# CAN-to-CAN.net
KiCad netlist of a schematic drawn in Altium Designer
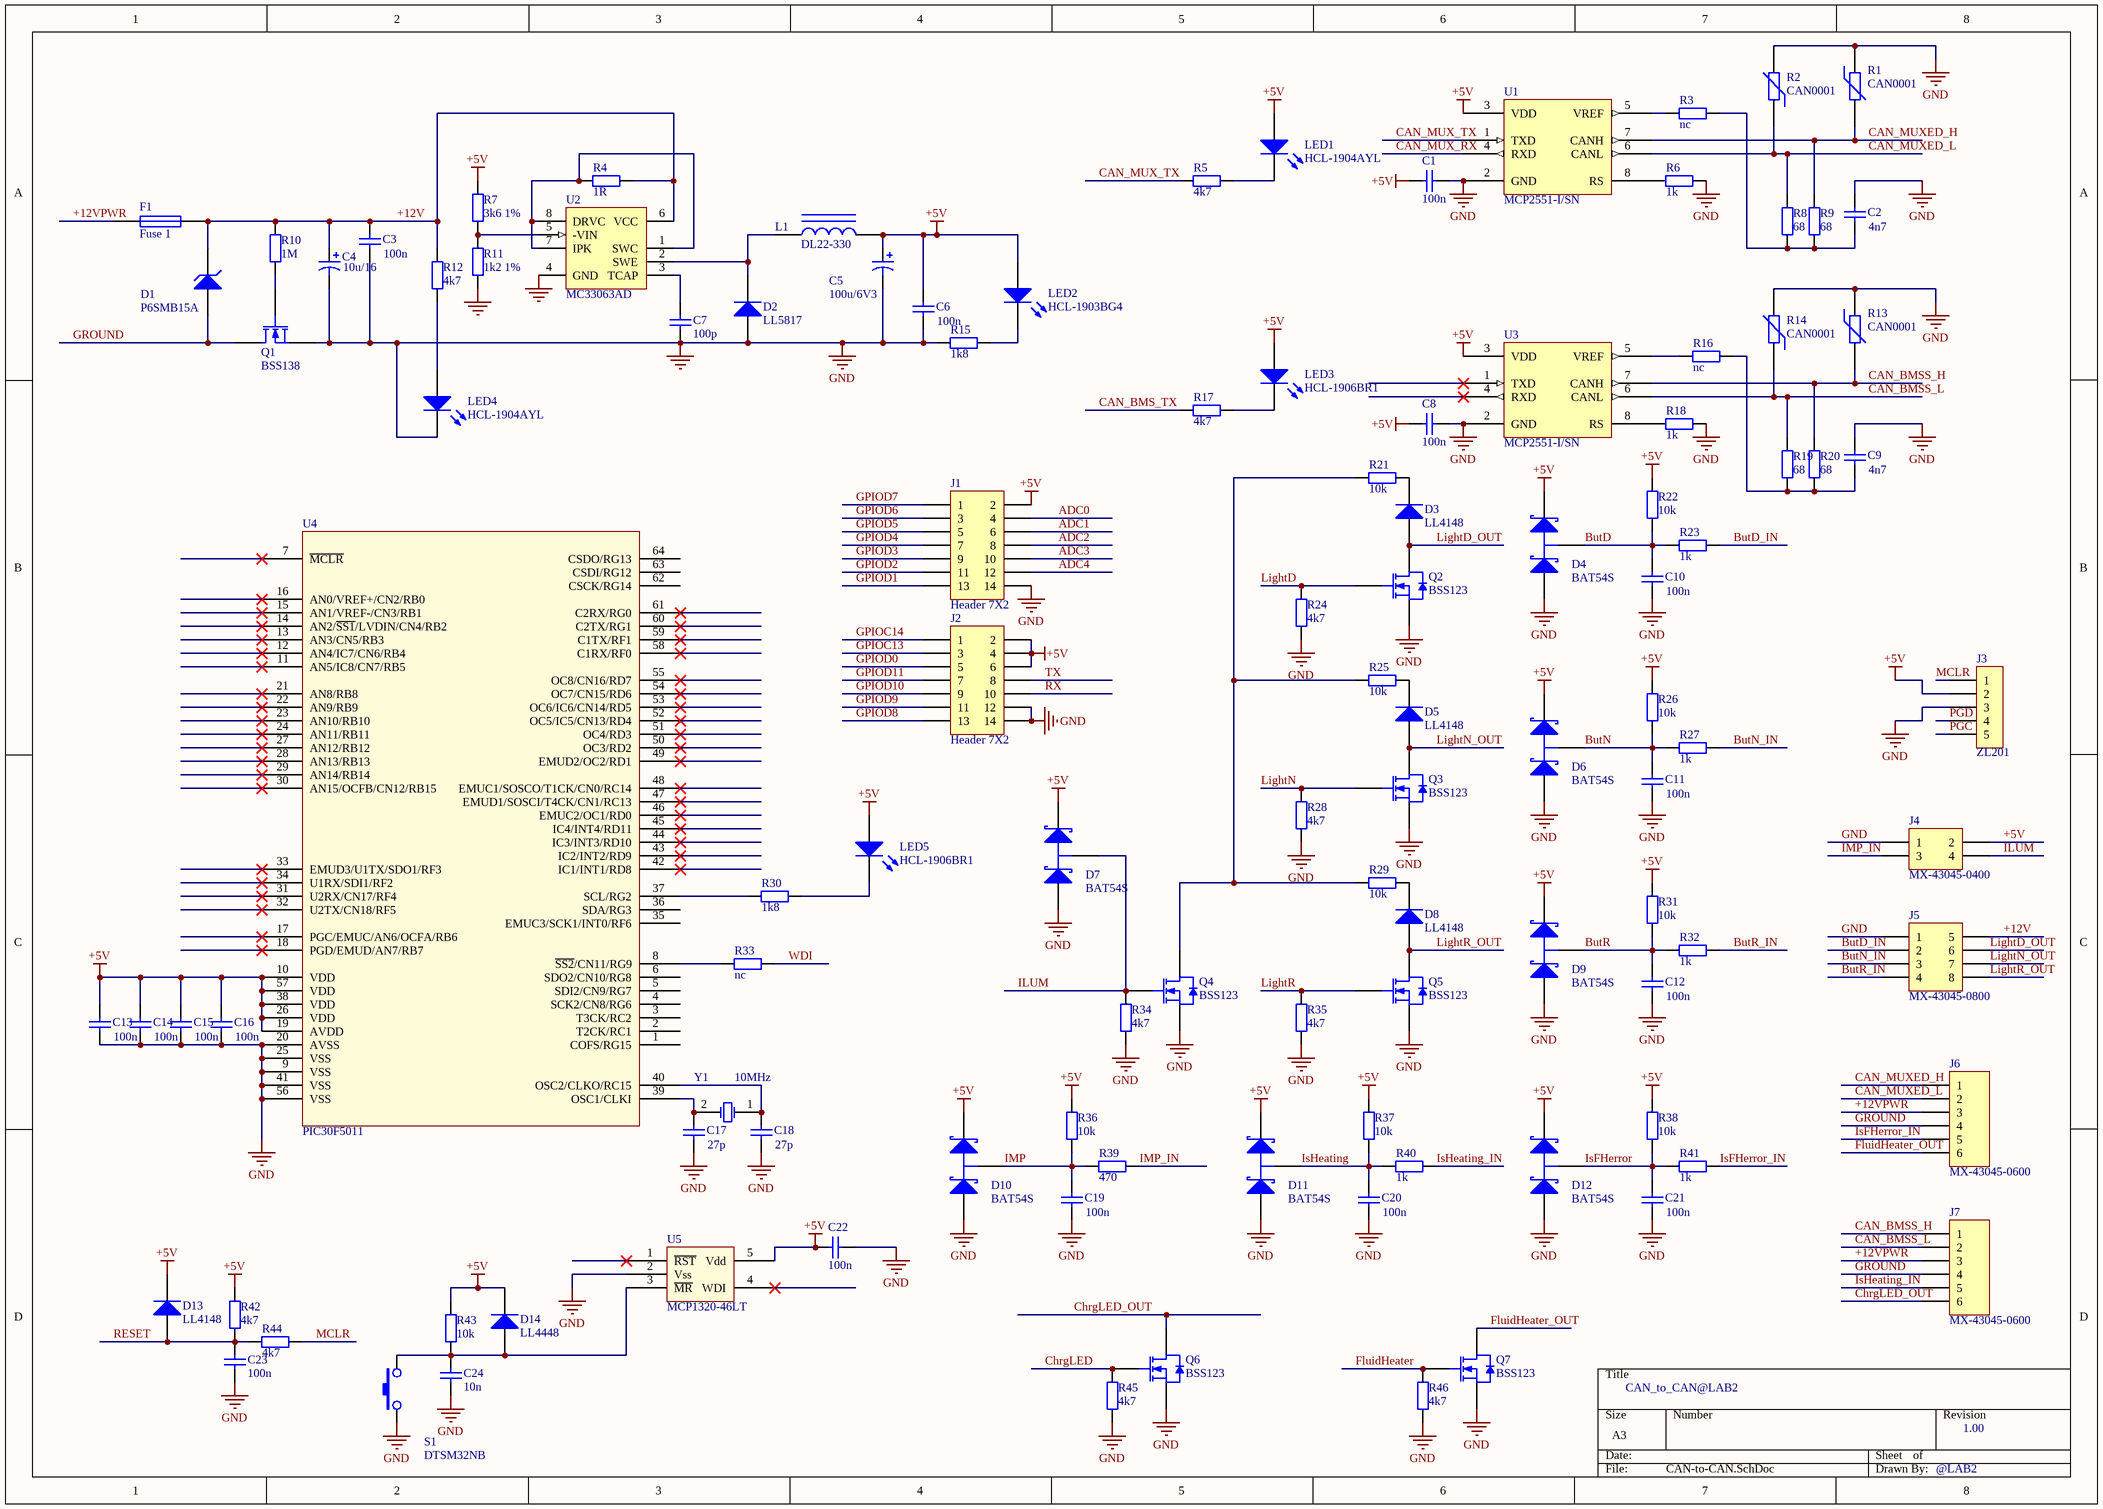
[diagram p0: CAN-to-CAN.SchDoc]

(export (version "E")
  (design (tool "Eeschema 10.0.6"))
  (components
    (comp (ref "C1")
      (value "100n")
      (footprint "0603")
      (description "Capacitor")
      (fields (field (name "PUBLISHER") "Altium Limited"))
      (libsource (lib "Miscellaneous Devices") (part "Cap"))
    )
    (comp (ref "C2")
      (value "4n7")
      (footprint "0603")
      (description "Capacitor")
      (fields (field (name "PUBLISHER") "Altium Limited"))
      (libsource (lib "Miscellaneous Devices") (part "Cap"))
    )
    (comp (ref "C3")
      (value "100n")
      (footprint "0402")
      (description "Capacitor")
      (fields (field (name "PUBLISHER") "Altium Limited"))
      (libsource (lib "Miscellaneous Devices") (part "Cap"))
    )
    (comp (ref "C4")
      (value "10u/16")
      (footprint "0402")
      (description "Polarized Capacitor (Radial)")
      (fields (field (name "PUBLISHER") "Altium Limited"))
      (libsource (lib "Miscellaneous Devices") (part "Cap Pol1"))
    )
    (comp (ref "C5")
      (value "100u/6V3")
      (footprint "0402")
      (description "Polarized Capacitor (Radial)")
      (fields (field (name "PUBLISHER") "Altium Limited"))
      (libsource (lib "Miscellaneous Devices") (part "Cap Pol1"))
    )
    (comp (ref "C6")
      (value "100n")
      (footprint "0603")
      (description "Capacitor")
      (fields (field (name "PUBLISHER") "Altium Limited"))
      (libsource (lib "Miscellaneous Devices") (part "Cap"))
    )
    (comp (ref "C7")
      (value "100p")
      (footprint "0603")
      (description "Capacitor")
      (fields (field (name "PUBLISHER") "Altium Limited"))
      (libsource (lib "Miscellaneous Devices") (part "Cap"))
    )
    (comp (ref "C8")
      (value "100n")
      (footprint "0603")
      (description "Capacitor")
      (fields (field (name "PUBLISHER") "Altium Limited"))
      (libsource (lib "Miscellaneous Devices") (part "Cap"))
    )
    (comp (ref "C9")
      (value "4n7")
      (footprint "0603")
      (description "Capacitor")
      (fields (field (name "PUBLISHER") "Altium Limited"))
      (libsource (lib "Miscellaneous Devices") (part "Cap"))
    )
    (comp (ref "C10")
      (value "100n")
      (footprint "0603")
      (description "Capacitor")
      (fields (field (name "PUBLISHER") "Altium Limited"))
      (libsource (lib "Miscellaneous Devices") (part "Cap"))
    )
    (comp (ref "C11")
      (value "100n")
      (footprint "0603")
      (description "Capacitor")
      (fields (field (name "PUBLISHER") "Altium Limited"))
      (libsource (lib "Miscellaneous Devices") (part "Cap"))
    )
    (comp (ref "C12")
      (value "100n")
      (footprint "0603")
      (description "Capacitor")
      (fields (field (name "PUBLISHER") "Altium Limited"))
      (libsource (lib "Miscellaneous Devices") (part "Cap"))
    )
    (comp (ref "C13")
      (value "100n")
      (footprint "0603")
      (description "Capacitor")
      (fields (field (name "PUBLISHER") "Altium Limited"))
      (libsource (lib "Miscellaneous Devices") (part "Cap"))
    )
    (comp (ref "C14")
      (value "100n")
      (footprint "0603")
      (description "Capacitor")
      (fields (field (name "PUBLISHER") "Altium Limited"))
      (libsource (lib "Miscellaneous Devices") (part "Cap"))
    )
    (comp (ref "C15")
      (value "100n")
      (footprint "0603")
      (description "Capacitor")
      (fields (field (name "PUBLISHER") "Altium Limited"))
      (libsource (lib "Miscellaneous Devices") (part "Cap"))
    )
    (comp (ref "C16")
      (value "100n")
      (footprint "0603")
      (description "Capacitor")
      (fields (field (name "PUBLISHER") "Altium Limited"))
      (libsource (lib "Miscellaneous Devices") (part "Cap"))
    )
    (comp (ref "C17")
      (value "27p")
      (footprint "0603")
      (description "Capacitor")
      (fields (field (name "PUBLISHER") "Altium Limited"))
      (libsource (lib "Miscellaneous Devices") (part "Cap"))
    )
    (comp (ref "C18")
      (value "27p")
      (footprint "0603")
      (description "Capacitor")
      (fields (field (name "PUBLISHER") "Altium Limited"))
      (libsource (lib "Miscellaneous Devices") (part "Cap"))
    )
    (comp (ref "C19")
      (value "100n")
      (footprint "0603")
      (description "Capacitor")
      (fields (field (name "PUBLISHER") "Altium Limited"))
      (libsource (lib "Miscellaneous Devices") (part "Cap"))
    )
    (comp (ref "C20")
      (value "100n")
      (footprint "0603")
      (description "Capacitor")
      (fields (field (name "PUBLISHER") "Altium Limited"))
      (libsource (lib "Miscellaneous Devices") (part "Cap"))
    )
    (comp (ref "C21")
      (value "100n")
      (footprint "0603")
      (description "Capacitor")
      (fields (field (name "PUBLISHER") "Altium Limited"))
      (libsource (lib "Miscellaneous Devices") (part "Cap"))
    )
    (comp (ref "C22")
      (value "100n")
      (footprint "0603")
      (description "Capacitor")
      (fields (field (name "PUBLISHER") "Altium Limited"))
      (libsource (lib "Miscellaneous Devices") (part "Cap"))
    )
    (comp (ref "C23")
      (value "100n")
      (footprint "0603")
      (description "Capacitor")
      (fields (field (name "PUBLISHER") "Altium Limited"))
      (libsource (lib "Miscellaneous Devices") (part "Cap"))
    )
    (comp (ref "C24")
      (value "10n")
      (footprint "0603")
      (description "Capacitor")
      (fields (field (name "PUBLISHER") "Altium Limited"))
      (libsource (lib "Miscellaneous Devices") (part "Cap"))
    )
    (comp (ref "D1")
      (value "P6SMB15A")
      (footprint "SMB")
      (description "Zener Diode")
      (fields (field (name "PUBLISHER") "Altium Limited"))
      (libsource (lib "Miscellaneous Devices") (part "D Zener"))
    )
    (comp (ref "D2")
      (value "LL5817")
      (footprint "DIODE_SMC")
      (description "High Conductance Fast Diode")
      (fields (field (name "PUBLISHER") "Altium Limited"))
      (libsource (lib "FSC Discrete Diode") (part "1N4148"))
    )
    (comp (ref "D3")
      (value "LL4148")
      (footprint "DIODE_SMC")
      (description "High Conductance Fast Diode")
      (fields (field (name "PUBLISHER") "Altium Limited"))
      (libsource (lib "FSC Discrete Diode") (part "1N4148"))
    )
    (comp (ref "D4")
      (value "BAT54S")
      (footprint "SOT-23_M")
      (description "Schottky Barrier Double Diode")
      (fields (field (name "PUBLISHER") "Altium Limited"))
      (libsource (lib "Philips Discrete Diode - Schottky") (part "BAT54S"))
    )
    (comp (ref "D5")
      (value "LL4148")
      (footprint "DIODE_SMC")
      (description "High Conductance Fast Diode")
      (fields (field (name "PUBLISHER") "Altium Limited"))
      (libsource (lib "FSC Discrete Diode") (part "1N4148"))
    )
    (comp (ref "D6")
      (value "BAT54S")
      (footprint "SOT23_M")
      (description "Schottky Barrier Double Diode")
      (fields (field (name "PUBLISHER") "Altium Limited"))
      (libsource (lib "Philips Discrete Diode - Schottky") (part "BAT54S"))
    )
    (comp (ref "D7")
      (value "BAT54S")
      (footprint "SOT23_M")
      (description "Schottky Barrier Double Diode")
      (fields (field (name "PUBLISHER") "Altium Limited"))
      (libsource (lib "Philips Discrete Diode - Schottky") (part "BAT54S"))
    )
    (comp (ref "D8")
      (value "LL4148")
      (footprint "DIODE_SMC")
      (description "High Conductance Fast Diode")
      (fields (field (name "PUBLISHER") "Altium Limited"))
      (libsource (lib "FSC Discrete Diode") (part "1N4148"))
    )
    (comp (ref "D9")
      (value "BAT54S")
      (footprint "SOT23_M")
      (description "Schottky Barrier Double Diode")
      (fields (field (name "PUBLISHER") "Altium Limited"))
      (libsource (lib "Philips Discrete Diode - Schottky") (part "BAT54S"))
    )
    (comp (ref "D10")
      (value "BAT54S")
      (footprint "SOT23_M")
      (description "Schottky Barrier Double Diode")
      (fields (field (name "PUBLISHER") "Altium Limited"))
      (libsource (lib "Philips Discrete Diode - Schottky") (part "BAT54S"))
    )
    (comp (ref "D11")
      (value "BAT54S")
      (footprint "SOT23_M")
      (description "Schottky Barrier Double Diode")
      (fields (field (name "PUBLISHER") "Altium Limited"))
      (libsource (lib "Philips Discrete Diode - Schottky") (part "BAT54S"))
    )
    (comp (ref "D12")
      (value "BAT54S")
      (footprint "SOT23_M")
      (description "Schottky Barrier Double Diode")
      (fields (field (name "PUBLISHER") "Altium Limited"))
      (libsource (lib "Philips Discrete Diode - Schottky") (part "BAT54S"))
    )
    (comp (ref "D13")
      (value "LL4148")
      (footprint "DIODE_SMC")
      (description "High Conductance Fast Diode")
      (fields (field (name "PUBLISHER") "Altium Limited"))
      (libsource (lib "FSC Discrete Diode") (part "1N4148"))
    )
    (comp (ref "D14")
      (value "LL4448")
      (footprint "DIODE_SMC")
      (description "Default Diode")
      (fields (field (name "PUBLISHER") "Altium Limited"))
      (libsource (lib "Miscellaneous Devices") (part "Diode"))
    )
    (comp (ref "F1")
      (value "Fuse 1")
      (footprint "1812")
      (description "Fuse")
      (fields (field (name "PUBLISHER") "Altium Limited"))
      (libsource (lib "Miscellaneous Devices") (part "Fuse 1"))
    )
    (comp (ref "J1")
      (value "Header 7X2")
      (footprint "HDR2X7")
      (description "Header, 7-Pin, Dual row")
      (fields (field (name "PUBLISHER") "Altium Limited"))
      (libsource (lib "Miscellaneous Connectors") (part "Header 7X2"))
    )
    (comp (ref "J2")
      (value "Header 7X2")
      (footprint "HDR2X7")
      (description "Header, 7-Pin, Dual row")
      (fields (field (name "PUBLISHER") "Altium Limited"))
      (libsource (lib "Miscellaneous Connectors") (part "Header 7X2"))
    )
    (comp (ref "J3")
      (value "ZL201")
      (footprint "HDR1X5")
      (description "Connector")
      (libsource (lib "*") (part "CON5"))
    )
    (comp (ref "J4")
      (value "MX-43045-0400")
      (footprint "SOT-343_M")
      (description "Header, 2-Pin, Dual row")
      (fields (field (name "PUBLISHER") "Altium Limited"))
      (libsource (lib "Miscellaneous Connectors") (part "Header 2X2"))
    )
    (comp (ref "J5")
      (value "MX-43045-0800")
      (footprint "DB008_M")
      (description "Header, 4-Pin, Dual row")
      (fields (field (name "PUBLISHER") "Altium Limited"))
      (libsource (lib "Miscellaneous Connectors") (part "Header 4X2A"))
    )
    (comp (ref "J6")
      (value "MX-43045-0600")
      (footprint "Miscellaneous Connectors:HDR1X6")
      (description "Header, 6-Pin")
      (fields (field (name "PUBLISHER") "Altium Limited"))
      (libsource (lib "Miscellaneous Connectors") (part "Header 6"))
    )
    (comp (ref "J7")
      (value "MX-43045-0600")
      (footprint "Miscellaneous Connectors:HDR1X6")
      (description "Header, 6-Pin")
      (fields (field (name "PUBLISHER") "Altium Limited"))
      (libsource (lib "Miscellaneous Connectors") (part "Header 6"))
    )
    (comp (ref "L1")
      (value "DL22-330")
      (footprint "INDC1608L")
      (description "Magnetic-Core Inductor")
      (fields (field (name "PUBLISHER") "Altium Limited"))
      (libsource (lib "Miscellaneous Devices") (part "Inductor Iron"))
    )
    (comp (ref "LED1")
      (value "HCL-1904AYL")
      (footprint "0603")
      (description "Typical BLUE SiC LED")
      (fields (field (name "PUBLISHER") "Altium Limited"))
      (libsource (lib "Miscellaneous Devices") (part "LED3"))
    )
    (comp (ref "LED2")
      (value "HCL-1903BG4")
      (footprint "0603")
      (description "Typical BLUE SiC LED")
      (fields (field (name "PUBLISHER") "Altium Limited"))
      (libsource (lib "Miscellaneous Devices") (part "LED3"))
    )
    (comp (ref "LED3")
      (value "HCL-1906BR1")
      (footprint "0603")
      (description "Typical BLUE SiC LED")
      (fields (field (name "PUBLISHER") "Altium Limited"))
      (libsource (lib "Miscellaneous Devices") (part "LED3"))
    )
    (comp (ref "LED4")
      (value "HCL-1904AYL")
      (footprint "0603")
      (description "Typical BLUE SiC LED")
      (fields (field (name "PUBLISHER") "Altium Limited"))
      (libsource (lib "Miscellaneous Devices") (part "LED3"))
    )
    (comp (ref "LED5")
      (value "HCL-1906BR1")
      (footprint "0603")
      (description "Typical BLUE SiC LED")
      (fields (field (name "PUBLISHER") "Altium Limited"))
      (libsource (lib "Miscellaneous Devices") (part "LED3"))
    )
    (comp (ref "Q1")
      (value "BSS138")
      (footprint "SOT23_M")
      (description "N-Channel Enhancement Mode Vertical DMOS FET")
      (fields (field (name "PUBLISHER") "Altium Limited"))
      (libsource (lib "Zetex Discrete MOSFET") (part "BSS138"))
    )
    (comp (ref "Q2")
      (value "BSS123")
      (footprint "SOT23_M")
      (description "N-channel Enhancement Mode Vertical D-MOSFET")
      (fields (field (name "PUBLISHER") "Altium Limited"))
      (libsource (lib "Philips Discrete MOSFET - Low Power") (part "BSS123"))
    )
    (comp (ref "Q3")
      (value "BSS123")
      (footprint "SOT23_M")
      (description "N-channel Enhancement Mode Vertical D-MOSFET")
      (fields (field (name "PUBLISHER") "Altium Limited"))
      (libsource (lib "Philips Discrete MOSFET - Low Power") (part "BSS123"))
    )
    (comp (ref "Q4")
      (value "BSS123")
      (footprint "SOT23_M")
      (description "N-channel Enhancement Mode Vertical D-MOSFET")
      (fields (field (name "PUBLISHER") "Altium Limited"))
      (libsource (lib "Philips Discrete MOSFET - Low Power") (part "BSS123"))
    )
    (comp (ref "Q5")
      (value "BSS123")
      (footprint "SOT23_M")
      (description "N-channel Enhancement Mode Vertical D-MOSFET")
      (fields (field (name "PUBLISHER") "Altium Limited"))
      (libsource (lib "Philips Discrete MOSFET - Low Power") (part "BSS123"))
    )
    (comp (ref "Q6")
      (value "BSS123")
      (footprint "SOT23_M")
      (description "N-channel Enhancement Mode Vertical D-MOSFET")
      (fields (field (name "PUBLISHER") "Altium Limited"))
      (libsource (lib "Philips Discrete MOSFET - Low Power") (part "BSS123"))
    )
    (comp (ref "Q7")
      (value "BSS123")
      (footprint "SOT23_M")
      (description "N-channel Enhancement Mode Vertical D-MOSFET")
      (fields (field (name "PUBLISHER") "Altium Limited"))
      (libsource (lib "Philips Discrete MOSFET - Low Power") (part "BSS123"))
    )
    (comp (ref "R1")
      (value "CAN0001")
      (footprint "0603")
      (description "Varistor (Voltage-Sensitive Resistor)")
      (fields (field (name "PUBLISHER") "Altium Limited"))
      (libsource (lib "Miscellaneous Devices") (part "Res Varistor"))
    )
    (comp (ref "R2")
      (value "CAN0001")
      (footprint "0603")
      (description "Varistor (Voltage-Sensitive Resistor)")
      (fields (field (name "PUBLISHER") "Altium Limited"))
      (libsource (lib "Miscellaneous Devices") (part "Res Varistor"))
    )
    (comp (ref "R3")
      (value "nc")
      (footprint "0603")
      (description "Resistor")
      (fields (field (name "PUBLISHER") "Altium Limited"))
      (libsource (lib "") (part "Res2_3"))
    )
    (comp (ref "R4")
      (value "1R")
      (footprint "12Z-2010")
      (description "Resistor")
      (fields (field (name "PUBLISHER") "Altium Limited"))
      (libsource (lib "") (part "Res2_3"))
    )
    (comp (ref "R5")
      (value "4k7")
      (footprint "0603")
      (description "Resistor")
      (fields (field (name "PUBLISHER") "Altium Limited"))
      (libsource (lib "") (part "Res2_1"))
    )
    (comp (ref "R6")
      (value "1k")
      (footprint "0603")
      (description "Resistor")
      (fields (field (name "PUBLISHER") "Altium Limited"))
      (libsource (lib "") (part "Res2_3"))
    )
    (comp (ref "R7")
      (value "3k6 1%")
      (footprint "0603")
      (description "Resistor")
      (fields (field (name "PUBLISHER") "Altium Limited"))
      (libsource (lib "Miscellaneous Devices") (part "Res2"))
    )
    (comp (ref "R8")
      (value "68")
      (footprint "0603")
      (description "Resistor")
      (fields (field (name "PUBLISHER") "Altium Limited"))
      (libsource (lib "Miscellaneous Devices") (part "Res2"))
    )
    (comp (ref "R9")
      (value "68")
      (footprint "0603")
      (description "Resistor")
      (fields (field (name "PUBLISHER") "Altium Limited"))
      (libsource (lib "Miscellaneous Devices") (part "Res2"))
    )
    (comp (ref "R10")
      (value "1M")
      (footprint "0603")
      (description "Resistor")
      (fields (field (name "PUBLISHER") "Altium Limited"))
      (libsource (lib "Miscellaneous Devices") (part "Res2"))
    )
    (comp (ref "R11")
      (value "1k2 1%")
      (footprint "0603")
      (description "Resistor")
      (fields (field (name "PUBLISHER") "Altium Limited"))
      (libsource (lib "") (part "Res2_2"))
    )
    (comp (ref "R12")
      (value "4k7")
      (footprint "0603")
      (description "Resistor")
      (fields (field (name "PUBLISHER") "Altium Limited"))
      (libsource (lib "Miscellaneous Devices") (part "Res2"))
    )
    (comp (ref "R13")
      (value "CAN0001")
      (footprint "0603")
      (description "Varistor (Voltage-Sensitive Resistor)")
      (fields (field (name "PUBLISHER") "Altium Limited"))
      (libsource (lib "Miscellaneous Devices") (part "Res Varistor"))
    )
    (comp (ref "R14")
      (value "CAN0001")
      (footprint "0603")
      (description "Varistor (Voltage-Sensitive Resistor)")
      (fields (field (name "PUBLISHER") "Altium Limited"))
      (libsource (lib "Miscellaneous Devices") (part "Res Varistor"))
    )
    (comp (ref "R15")
      (value "1k8")
      (footprint "0603")
      (description "Resistor")
      (fields (field (name "PUBLISHER") "Altium Limited"))
      (libsource (lib "") (part "Res2_1"))
    )
    (comp (ref "R16")
      (value "nc")
      (footprint "0603")
      (description "Resistor")
      (fields (field (name "PUBLISHER") "Altium Limited"))
      (libsource (lib "") (part "Res2_3"))
    )
    (comp (ref "R17")
      (value "4k7")
      (footprint "0603")
      (description "Resistor")
      (fields (field (name "PUBLISHER") "Altium Limited"))
      (libsource (lib "") (part "Res2_1"))
    )
    (comp (ref "R18")
      (value "1k")
      (footprint "0603")
      (description "Resistor")
      (fields (field (name "PUBLISHER") "Altium Limited"))
      (libsource (lib "") (part "Res2_3"))
    )
    (comp (ref "R19")
      (value "68")
      (footprint "0603")
      (description "Resistor")
      (fields (field (name "PUBLISHER") "Altium Limited"))
      (libsource (lib "Miscellaneous Devices") (part "Res2"))
    )
    (comp (ref "R20")
      (value "68")
      (footprint "0603")
      (description "Resistor")
      (fields (field (name "PUBLISHER") "Altium Limited"))
      (libsource (lib "Miscellaneous Devices") (part "Res2"))
    )
    (comp (ref "R21")
      (value "10k")
      (footprint "0603")
      (description "Resistor")
      (fields (field (name "PUBLISHER") "Altium Limited"))
      (libsource (lib "") (part "Res2_3"))
    )
    (comp (ref "R22")
      (value "10k")
      (footprint "0603")
      (description "Resistor")
      (fields (field (name "PUBLISHER") "Altium Limited"))
      (libsource (lib "Miscellaneous Devices") (part "Res2"))
    )
    (comp (ref "R23")
      (value "1k")
      (footprint "0603")
      (description "Resistor")
      (fields (field (name "PUBLISHER") "Altium Limited"))
      (libsource (lib "") (part "Res2_1"))
    )
    (comp (ref "R24")
      (value "4k7")
      (footprint "0603")
      (description "Resistor")
      (fields (field (name "PUBLISHER") "Altium Limited"))
      (libsource (lib "Miscellaneous Devices") (part "Res2"))
    )
    (comp (ref "R25")
      (value "10k")
      (footprint "0603")
      (description "Resistor")
      (fields (field (name "PUBLISHER") "Altium Limited"))
      (libsource (lib "") (part "Res2_3"))
    )
    (comp (ref "R26")
      (value "10k")
      (footprint "0603")
      (description "Resistor")
      (fields (field (name "PUBLISHER") "Altium Limited"))
      (libsource (lib "Miscellaneous Devices") (part "Res2"))
    )
    (comp (ref "R27")
      (value "1k")
      (footprint "0603")
      (description "Resistor")
      (fields (field (name "PUBLISHER") "Altium Limited"))
      (libsource (lib "") (part "Res2_1"))
    )
    (comp (ref "R28")
      (value "4k7")
      (footprint "0603")
      (description "Resistor")
      (fields (field (name "PUBLISHER") "Altium Limited"))
      (libsource (lib "Miscellaneous Devices") (part "Res2"))
    )
    (comp (ref "R29")
      (value "10k")
      (footprint "0603")
      (description "Resistor")
      (fields (field (name "PUBLISHER") "Altium Limited"))
      (libsource (lib "") (part "Res2_3"))
    )
    (comp (ref "R30")
      (value "1k8")
      (footprint "0603")
      (description "Resistor")
      (fields (field (name "PUBLISHER") "Altium Limited"))
      (libsource (lib "") (part "Res2_1"))
    )
    (comp (ref "R31")
      (value "10k")
      (footprint "0603")
      (description "Resistor")
      (fields (field (name "PUBLISHER") "Altium Limited"))
      (libsource (lib "Miscellaneous Devices") (part "Res2"))
    )
    (comp (ref "R32")
      (value "1k")
      (footprint "0603")
      (description "Resistor")
      (fields (field (name "PUBLISHER") "Altium Limited"))
      (libsource (lib "") (part "Res2_1"))
    )
    (comp (ref "R33")
      (value "nc")
      (footprint "0603")
      (description "Resistor")
      (fields (field (name "PUBLISHER") "Altium Limited"))
      (libsource (lib "") (part "Res2_1"))
    )
    (comp (ref "R34")
      (value "4k7")
      (footprint "0603")
      (description "Resistor")
      (fields (field (name "PUBLISHER") "Altium Limited"))
      (libsource (lib "Miscellaneous Devices") (part "Res2"))
    )
    (comp (ref "R35")
      (value "4k7")
      (footprint "0603")
      (description "Resistor")
      (fields (field (name "PUBLISHER") "Altium Limited"))
      (libsource (lib "Miscellaneous Devices") (part "Res2"))
    )
    (comp (ref "R36")
      (value "10k")
      (footprint "0603")
      (description "Resistor")
      (fields (field (name "PUBLISHER") "Altium Limited"))
      (libsource (lib "Miscellaneous Devices") (part "Res2"))
    )
    (comp (ref "R37")
      (value "10k")
      (footprint "0603")
      (description "Resistor")
      (fields (field (name "PUBLISHER") "Altium Limited"))
      (libsource (lib "Miscellaneous Devices") (part "Res2"))
    )
    (comp (ref "R38")
      (value "10k")
      (footprint "0603")
      (description "Resistor")
      (fields (field (name "PUBLISHER") "Altium Limited"))
      (libsource (lib "Miscellaneous Devices") (part "Res2"))
    )
    (comp (ref "R39")
      (value "470")
      (footprint "0603")
      (description "Resistor")
      (fields (field (name "PUBLISHER") "Altium Limited"))
      (libsource (lib "") (part "Res2_1"))
    )
    (comp (ref "R40")
      (value "1k")
      (footprint "0603")
      (description "Resistor")
      (fields (field (name "PUBLISHER") "Altium Limited"))
      (libsource (lib "") (part "Res2_1"))
    )
    (comp (ref "R41")
      (value "1k")
      (footprint "0603")
      (description "Resistor")
      (fields (field (name "PUBLISHER") "Altium Limited"))
      (libsource (lib "") (part "Res2_1"))
    )
    (comp (ref "R42")
      (value "4k7")
      (footprint "0603")
      (description "Resistor")
      (fields (field (name "PUBLISHER") "Altium Limited"))
      (libsource (lib "Miscellaneous Devices") (part "Res2"))
    )
    (comp (ref "R43")
      (value "10k")
      (footprint "0603")
      (description "Resistor")
      (fields (field (name "PUBLISHER") "Altium Limited"))
      (libsource (lib "") (part "Res2_2"))
    )
    (comp (ref "R44")
      (value "4k7")
      (footprint "0603")
      (description "Resistor")
      (fields (field (name "PUBLISHER") "Altium Limited"))
      (libsource (lib "") (part "Res2_1"))
    )
    (comp (ref "R45")
      (value "4k7")
      (footprint "0603")
      (description "Resistor")
      (fields (field (name "PUBLISHER") "Altium Limited"))
      (libsource (lib "Miscellaneous Devices") (part "Res2"))
    )
    (comp (ref "R46")
      (value "4k7")
      (footprint "0603")
      (description "Resistor")
      (fields (field (name "PUBLISHER") "Altium Limited"))
      (libsource (lib "Miscellaneous Devices") (part "Res2"))
    )
    (comp (ref "S1")
      (value "DTSM32NB")
      (footprint "SPST-2")
      (description "Switch PushButton")
      (libsource (lib "*") (part "PUSHB"))
    )
    (comp (ref "U1")
      (value "MCP2551-I/SN")
      (footprint "DB008_M")
      (description "High Speed CAN Transceiver, 8-Pin Plastic SOIC, Industrial Grade")
      (fields (field (name "PUBLISHER") "Altium Limited"))
      (libsource (lib "Microchip Interface Line Transceiver") (part "MCP2551-I/SN"))
    )
    (comp (ref "U2")
      (value "MC33063AD")
      (footprint "SO8_N")
      (description "DC-to-DC Converter Control Circuit")
      (fields (field (name "PUBLISHER") "Altium Limited"))
      (libsource (lib "Motorola Power Mgt DC-DC Converter") (part "MC33063AD"))
    )
    (comp (ref "U3")
      (value "MCP2551-I/SN")
      (footprint "SO8_N")
      (description "High Speed CAN Transceiver, 8-Pin Plastic SOIC, Industrial Grade")
      (fields (field (name "PUBLISHER") "Altium Limited"))
      (libsource (lib "Microchip Interface Line Transceiver") (part "MCP2551-I/SN"))
    )
    (comp (ref "U4")
      (value "PIC30F5011")
      (footprint "ST-64-2_M")
      (description "PIC30F5011 - Up")
      (libsource (lib "X-Tro's Misc") (part "PIC30F5011"))
    )
    (comp (ref "U5")
      (value "MCP1320-46LT")
      (footprint "SOT23-5")
      (libsource (lib "X-Tro's Misc") (part "MCP1320"))
    )
    (comp (ref "Y1")
      (value "10MHz")
      (footprint "XTALSMD2")
      (description "Crystal Oscillator")
      (fields (field (name "PUBLISHER") "Altium Limited"))
      (libsource (lib "Miscellaneous Devices") (part "XTAL"))
    )
  )
  (nets
    (net (code "1") (name "+5V") (class "Default")
      (node (ref "C1") (pin "1") (pinfunction "1_1") (pintype "passive"))
      (node (ref "C13") (pin "1") (pinfunction "1_1") (pintype "passive"))
      (node (ref "C14") (pin "1") (pinfunction "1_1") (pintype "passive"))
      (node (ref "C15") (pin "1") (pinfunction "1_1") (pintype "passive"))
      (node (ref "C16") (pin "1") (pinfunction "1_1") (pintype "passive"))
      (node (ref "C22") (pin "1") (pinfunction "1_1") (pintype "passive"))
      (node (ref "C5") (pin "1") (pinfunction "1_1") (pintype "passive"))
      (node (ref "C6") (pin "1") (pinfunction "1_1") (pintype "passive"))
      (node (ref "C8") (pin "1") (pinfunction "1_1") (pintype "passive"))
      (node (ref "D10") (pin "2") (pinfunction "K_2") (pintype "passive"))
      (node (ref "D11") (pin "2") (pinfunction "K_2") (pintype "passive"))
      (node (ref "D12") (pin "2") (pinfunction "K_2") (pintype "passive"))
      (node (ref "D13") (pin "2") (pinfunction "K_2") (pintype "passive"))
      (node (ref "D14") (pin "2") (pinfunction "K_2") (pintype "passive"))
      (node (ref "D4") (pin "2") (pinfunction "K_2") (pintype "passive"))
      (node (ref "D6") (pin "2") (pinfunction "K_2") (pintype "passive"))
      (node (ref "D7") (pin "2") (pinfunction "K_2") (pintype "passive"))
      (node (ref "D9") (pin "2") (pinfunction "K_2") (pintype "passive"))
      (node (ref "J1") (pin "2") (pinfunction "2_2") (pintype "passive"))
      (node (ref "J2") (pin "2") (pinfunction "2_2") (pintype "passive"))
      (node (ref "J2") (pin "4") (pinfunction "4_4") (pintype "passive"))
      (node (ref "J2") (pin "6") (pinfunction "6_6") (pintype "passive"))
      (node (ref "J3") (pin "2") (pinfunction "2_2") (pintype "passive"))
      (node (ref "J4") (pin "2") (pinfunction "2_2") (pintype "passive"))
      (node (ref "L1") (pin "2") (pinfunction "2_2") (pintype "passive"))
      (node (ref "LED1") (pin "1") (pinfunction "A_1") (pintype "passive"))
      (node (ref "LED2") (pin "1") (pinfunction "A_1") (pintype "passive"))
      (node (ref "LED3") (pin "1") (pinfunction "A_1") (pintype "passive"))
      (node (ref "LED5") (pin "1") (pinfunction "A_1") (pintype "passive"))
      (node (ref "R22") (pin "1") (pinfunction "1_1") (pintype "passive"))
      (node (ref "R26") (pin "1") (pinfunction "1_1") (pintype "passive"))
      (node (ref "R31") (pin "1") (pinfunction "1_1") (pintype "passive"))
      (node (ref "R36") (pin "1") (pinfunction "1_1") (pintype "passive"))
      (node (ref "R37") (pin "1") (pinfunction "1_1") (pintype "passive"))
      (node (ref "R38") (pin "1") (pinfunction "1_1") (pintype "passive"))
      (node (ref "R42") (pin "1") (pinfunction "1_1") (pintype "passive"))
      (node (ref "R43") (pin "2") (pinfunction "2_2") (pintype "passive"))
      (node (ref "R7") (pin "1") (pinfunction "1_1") (pintype "passive"))
      (node (ref "U1") (pin "3") (pinfunction "VDD_3") (pintype "power_in"))
      (node (ref "U3") (pin "3") (pinfunction "VDD_3") (pintype "power_in"))
      (node (ref "U4") (pin "10") (pinfunction "VDD_10") (pintype "passive"))
      (node (ref "U4") (pin "19") (pinfunction "AVDD_19") (pintype "passive"))
      (node (ref "U4") (pin "26") (pinfunction "VDD_26") (pintype "passive"))
      (node (ref "U4") (pin "38") (pinfunction "VDD_38") (pintype "passive"))
      (node (ref "U4") (pin "57") (pinfunction "VDD_57") (pintype "passive"))
      (node (ref "U5") (pin "5") (pinfunction "Vdd_5") (pintype "passive"))
    )
    (net (code "2") (name "/+12V") (class "Default")
      (node (ref "C3") (pin "1") (pinfunction "1_1") (pintype "passive"))
      (node (ref "C4") (pin "1") (pinfunction "1_1") (pintype "passive"))
      (node (ref "D1") (pin "2") (pinfunction "K_2") (pintype "passive"))
      (node (ref "F1") (pin "2") (pinfunction "2_2") (pintype "passive"))
      (node (ref "J5") (pin "5") (pinfunction "5_5") (pintype "passive"))
      (node (ref "R10") (pin "1") (pinfunction "1_1") (pintype "passive"))
      (node (ref "R12") (pin "1") (pinfunction "1_1") (pintype "passive"))
      (node (ref "R4") (pin "2") (pinfunction "2_2") (pintype "passive"))
      (node (ref "U2") (pin "6") (pinfunction "VCC_6") (pintype "power_in"))
    )
    (net (code "3") (name "/+12VPWR") (class "Default")
      (node (ref "F1") (pin "1") (pinfunction "1_1") (pintype "passive"))
      (node (ref "J6") (pin "3") (pinfunction "3_3") (pintype "passive"))
      (node (ref "J7") (pin "3") (pinfunction "3_3") (pintype "passive"))
    )
    (net (code "4") (name "/ADC0") (class "Default")
      (node (ref "J1") (pin "4") (pinfunction "4_4") (pintype "passive"))
    )
    (net (code "5") (name "/ADC1") (class "Default")
      (node (ref "J1") (pin "6") (pinfunction "6_6") (pintype "passive"))
    )
    (net (code "6") (name "/ADC2") (class "Default")
      (node (ref "J1") (pin "8") (pinfunction "8_8") (pintype "passive"))
    )
    (net (code "7") (name "/ADC3") (class "Default")
      (node (ref "J1") (pin "10") (pinfunction "10_10") (pintype "passive"))
    )
    (net (code "8") (name "/ADC4") (class "Default")
      (node (ref "J1") (pin "12") (pinfunction "12_12") (pintype "passive"))
    )
    (net (code "9") (name "/ButD") (class "Default")
      (node (ref "C10") (pin "1") (pinfunction "1_1") (pintype "passive"))
      (node (ref "D4") (pin "3") (pinfunction "C_3") (pintype "passive"))
      (node (ref "R22") (pin "2") (pinfunction "2_2") (pintype "passive"))
      (node (ref "R23") (pin "2") (pinfunction "2_2") (pintype "passive"))
    )
    (net (code "10") (name "/ButD_IN") (class "Default")
      (node (ref "J5") (pin "2") (pinfunction "2_2") (pintype "passive"))
      (node (ref "R23") (pin "1") (pinfunction "1_1") (pintype "passive"))
    )
    (net (code "11") (name "/ButN") (class "Default")
      (node (ref "C11") (pin "1") (pinfunction "1_1") (pintype "passive"))
      (node (ref "D6") (pin "3") (pinfunction "C_3") (pintype "passive"))
      (node (ref "R26") (pin "2") (pinfunction "2_2") (pintype "passive"))
      (node (ref "R27") (pin "2") (pinfunction "2_2") (pintype "passive"))
    )
    (net (code "12") (name "/ButN_IN") (class "Default")
      (node (ref "J5") (pin "3") (pinfunction "3_3") (pintype "passive"))
      (node (ref "R27") (pin "1") (pinfunction "1_1") (pintype "passive"))
    )
    (net (code "13") (name "/ButR") (class "Default")
      (node (ref "C12") (pin "1") (pinfunction "1_1") (pintype "passive"))
      (node (ref "D9") (pin "3") (pinfunction "C_3") (pintype "passive"))
      (node (ref "R31") (pin "2") (pinfunction "2_2") (pintype "passive"))
      (node (ref "R32") (pin "2") (pinfunction "2_2") (pintype "passive"))
    )
    (net (code "14") (name "/ButR_IN") (class "Default")
      (node (ref "J5") (pin "4") (pinfunction "4_4") (pintype "passive"))
      (node (ref "R32") (pin "1") (pinfunction "1_1") (pintype "passive"))
    )
    (net (code "15") (name "/CAN_BMSS_H") (class "Default")
      (node (ref "J7") (pin "1") (pinfunction "1_1") (pintype "passive"))
      (node (ref "R13") (pin "2") (pinfunction "2_2") (pintype "passive"))
      (node (ref "R20") (pin "1") (pinfunction "1_1") (pintype "passive"))
      (node (ref "U3") (pin "7") (pinfunction "CANH_7") (pintype "output"))
    )
    (net (code "16") (name "/CAN_BMSS_L") (class "Default")
      (node (ref "J7") (pin "2") (pinfunction "2_2") (pintype "passive"))
      (node (ref "R14") (pin "1") (pinfunction "1_1") (pintype "passive"))
      (node (ref "R19") (pin "1") (pinfunction "1_1") (pintype "passive"))
      (node (ref "U3") (pin "6") (pinfunction "CANL_6") (pintype "output"))
    )
    (net (code "17") (name "/CAN_BMS_TX") (class "Default")
      (node (ref "R17") (pin "2") (pinfunction "2_2") (pintype "passive"))
    )
    (net (code "18") (name "/CAN_MUXED_H") (class "Default")
      (node (ref "J6") (pin "1") (pinfunction "1_1") (pintype "passive"))
      (node (ref "R1") (pin "2") (pinfunction "2_2") (pintype "passive"))
      (node (ref "R9") (pin "1") (pinfunction "1_1") (pintype "passive"))
      (node (ref "U1") (pin "7") (pinfunction "CANH_7") (pintype "output"))
    )
    (net (code "19") (name "/CAN_MUXED_L") (class "Default")
      (node (ref "J6") (pin "2") (pinfunction "2_2") (pintype "passive"))
      (node (ref "R2") (pin "1") (pinfunction "1_1") (pintype "passive"))
      (node (ref "R8") (pin "1") (pinfunction "1_1") (pintype "passive"))
      (node (ref "U1") (pin "6") (pinfunction "CANL_6") (pintype "output"))
    )
    (net (code "20") (name "/CAN_MUX_RX") (class "Default")
      (node (ref "U1") (pin "4") (pinfunction "RXD_4") (pintype "output"))
    )
    (net (code "21") (name "/CAN_MUX_TX") (class "Default")
      (node (ref "R5") (pin "2") (pinfunction "2_2") (pintype "passive"))
      (node (ref "U1") (pin "1") (pinfunction "TXD_1") (pintype "input"))
    )
    (net (code "22") (name "/ChrgLED") (class "Default")
      (node (ref "Q6") (pin "3") (pinfunction "G_3") (pintype "passive"))
      (node (ref "R45") (pin "1") (pinfunction "1_1") (pintype "passive"))
    )
    (net (code "23") (name "/ChrgLED_OUT") (class "Default")
      (node (ref "J7") (pin "6") (pinfunction "6_6") (pintype "passive"))
      (node (ref "Q6") (pin "1") (pinfunction "D_1") (pintype "passive"))
    )
    (net (code "24") (name "/FluidHeater") (class "Default")
      (node (ref "Q7") (pin "3") (pinfunction "G_3") (pintype "passive"))
      (node (ref "R46") (pin "1") (pinfunction "1_1") (pintype "passive"))
    )
    (net (code "25") (name "/FluidHeater_OUT") (class "Default")
      (node (ref "J6") (pin "6") (pinfunction "6_6") (pintype "passive"))
      (node (ref "Q7") (pin "1") (pinfunction "D_1") (pintype "passive"))
    )
    (net (code "26") (name "/GPIOC13") (class "Default")
      (node (ref "J2") (pin "3") (pinfunction "3_3") (pintype "passive"))
    )
    (net (code "27") (name "/GPIOC14") (class "Default")
      (node (ref "J2") (pin "1") (pinfunction "1_1") (pintype "passive"))
    )
    (net (code "28") (name "/GPIOD0") (class "Default")
      (node (ref "J2") (pin "5") (pinfunction "5_5") (pintype "passive"))
    )
    (net (code "29") (name "/GPIOD1") (class "Default")
      (node (ref "J1") (pin "13") (pinfunction "13_13") (pintype "passive"))
    )
    (net (code "30") (name "/GPIOD2") (class "Default")
      (node (ref "J1") (pin "11") (pinfunction "11_11") (pintype "passive"))
    )
    (net (code "31") (name "/GPIOD3") (class "Default")
      (node (ref "J1") (pin "9") (pinfunction "9_9") (pintype "passive"))
    )
    (net (code "32") (name "/GPIOD4") (class "Default")
      (node (ref "J1") (pin "7") (pinfunction "7_7") (pintype "passive"))
    )
    (net (code "33") (name "/GPIOD5") (class "Default")
      (node (ref "J1") (pin "5") (pinfunction "5_5") (pintype "passive"))
    )
    (net (code "34") (name "/GPIOD6") (class "Default")
      (node (ref "J1") (pin "3") (pinfunction "3_3") (pintype "passive"))
    )
    (net (code "35") (name "/GPIOD7") (class "Default")
      (node (ref "J1") (pin "1") (pinfunction "1_1") (pintype "passive"))
    )
    (net (code "36") (name "/GPIOD8") (class "Default")
      (node (ref "J2") (pin "13") (pinfunction "13_13") (pintype "passive"))
    )
    (net (code "37") (name "/GPIOD9") (class "Default")
      (node (ref "J2") (pin "11") (pinfunction "11_11") (pintype "passive"))
    )
    (net (code "38") (name "/GPIOD10") (class "Default")
      (node (ref "J2") (pin "9") (pinfunction "9_9") (pintype "passive"))
    )
    (net (code "39") (name "/GPIOD11") (class "Default")
      (node (ref "J2") (pin "7") (pinfunction "7_7") (pintype "passive"))
    )
    (net (code "40") (name "/GROUND") (class "Default")
      (node (ref "D1") (pin "1") (pinfunction "A_1") (pintype "passive"))
      (node (ref "J6") (pin "4") (pinfunction "4_4") (pintype "passive"))
      (node (ref "J7") (pin "4") (pinfunction "4_4") (pintype "passive"))
      (node (ref "Q1") (pin "1") (pinfunction "D_1") (pintype "passive"))
    )
    (net (code "41") (name "/ILUM") (class "Default")
      (node (ref "D7") (pin "3") (pinfunction "C_3") (pintype "passive"))
      (node (ref "J4") (pin "4") (pinfunction "4_4") (pintype "passive"))
      (node (ref "Q4") (pin "3") (pinfunction "G_3") (pintype "passive"))
      (node (ref "R34") (pin "1") (pinfunction "1_1") (pintype "passive"))
    )
    (net (code "42") (name "/IMP") (class "Default")
      (node (ref "C19") (pin "1") (pinfunction "1_1") (pintype "passive"))
      (node (ref "D10") (pin "3") (pinfunction "C_3") (pintype "passive"))
      (node (ref "R36") (pin "2") (pinfunction "2_2") (pintype "passive"))
      (node (ref "R39") (pin "2") (pinfunction "2_2") (pintype "passive"))
    )
    (net (code "43") (name "/IMP_IN") (class "Default")
      (node (ref "J4") (pin "3") (pinfunction "3_3") (pintype "passive"))
      (node (ref "R39") (pin "1") (pinfunction "1_1") (pintype "passive"))
    )
    (net (code "44") (name "/IsFHerror") (class "Default")
      (node (ref "C21") (pin "1") (pinfunction "1_1") (pintype "passive"))
      (node (ref "D12") (pin "3") (pinfunction "C_3") (pintype "passive"))
      (node (ref "R38") (pin "2") (pinfunction "2_2") (pintype "passive"))
      (node (ref "R41") (pin "2") (pinfunction "2_2") (pintype "passive"))
    )
    (net (code "45") (name "/IsFHerror_IN") (class "Default")
      (node (ref "J6") (pin "5") (pinfunction "5_5") (pintype "passive"))
      (node (ref "R41") (pin "1") (pinfunction "1_1") (pintype "passive"))
    )
    (net (code "46") (name "/IsHeating") (class "Default")
      (node (ref "C20") (pin "1") (pinfunction "1_1") (pintype "passive"))
      (node (ref "D11") (pin "3") (pinfunction "C_3") (pintype "passive"))
      (node (ref "R37") (pin "2") (pinfunction "2_2") (pintype "passive"))
      (node (ref "R40") (pin "2") (pinfunction "2_2") (pintype "passive"))
    )
    (net (code "47") (name "/IsHeating_IN") (class "Default")
      (node (ref "J7") (pin "5") (pinfunction "5_5") (pintype "passive"))
      (node (ref "R40") (pin "1") (pinfunction "1_1") (pintype "passive"))
    )
    (net (code "48") (name "/LightD") (class "Default")
      (node (ref "Q2") (pin "3") (pinfunction "G_3") (pintype "passive"))
      (node (ref "R24") (pin "1") (pinfunction "1_1") (pintype "passive"))
    )
    (net (code "49") (name "/LightD_OUT") (class "Default")
      (node (ref "D3") (pin "1") (pinfunction "A_1") (pintype "passive"))
      (node (ref "J5") (pin "6") (pinfunction "6_6") (pintype "passive"))
      (node (ref "Q2") (pin "1") (pinfunction "D_1") (pintype "passive"))
    )
    (net (code "50") (name "/LightN") (class "Default")
      (node (ref "Q3") (pin "3") (pinfunction "G_3") (pintype "passive"))
      (node (ref "R28") (pin "1") (pinfunction "1_1") (pintype "passive"))
    )
    (net (code "51") (name "/LightN_OUT") (class "Default")
      (node (ref "D5") (pin "1") (pinfunction "A_1") (pintype "passive"))
      (node (ref "J5") (pin "7") (pinfunction "7_7") (pintype "passive"))
      (node (ref "Q3") (pin "1") (pinfunction "D_1") (pintype "passive"))
    )
    (net (code "52") (name "/LightR") (class "Default")
      (node (ref "Q5") (pin "3") (pinfunction "G_3") (pintype "passive"))
      (node (ref "R35") (pin "1") (pinfunction "1_1") (pintype "passive"))
    )
    (net (code "53") (name "/LightR_OUT") (class "Default")
      (node (ref "D8") (pin "1") (pinfunction "A_1") (pintype "passive"))
      (node (ref "J5") (pin "8") (pinfunction "8_8") (pintype "passive"))
      (node (ref "Q5") (pin "1") (pinfunction "D_1") (pintype "passive"))
    )
    (net (code "54") (name "/MCLR") (class "Default")
      (node (ref "J3") (pin "1") (pinfunction "1_1") (pintype "passive"))
      (node (ref "R44") (pin "1") (pinfunction "1_1") (pintype "passive"))
    )
    (net (code "55") (name "/PGC") (class "Default")
      (node (ref "J3") (pin "5") (pinfunction "5_5") (pintype "passive"))
    )
    (net (code "56") (name "/PGD") (class "Default")
      (node (ref "J3") (pin "4") (pinfunction "4_4") (pintype "passive"))
    )
    (net (code "57") (name "/RESET") (class "Default")
      (node (ref "C23") (pin "2") (pinfunction "2_2") (pintype "passive"))
      (node (ref "D13") (pin "1") (pinfunction "A_1") (pintype "passive"))
      (node (ref "R42") (pin "2") (pinfunction "2_2") (pintype "passive"))
      (node (ref "R44") (pin "2") (pinfunction "2_2") (pintype "passive"))
    )
    (net (code "58") (name "/RX") (class "Default")
      (node (ref "J2") (pin "10") (pinfunction "10_10") (pintype "passive"))
    )
    (net (code "59") (name "/TX") (class "Default")
      (node (ref "J2") (pin "8") (pinfunction "8_8") (pintype "passive"))
    )
    (net (code "60") (name "/WDI") (class "Default")
      (node (ref "R33") (pin "1") (pinfunction "1_1") (pintype "passive"))
    )
    (net (code "61") (name "GND") (class "Default")
      (node (ref "C1") (pin "2") (pinfunction "2_2") (pintype "passive"))
      (node (ref "C10") (pin "2") (pinfunction "2_2") (pintype "passive"))
      (node (ref "C11") (pin "2") (pinfunction "2_2") (pintype "passive"))
      (node (ref "C12") (pin "2") (pinfunction "2_2") (pintype "passive"))
      (node (ref "C13") (pin "2") (pinfunction "2_2") (pintype "passive"))
      (node (ref "C14") (pin "2") (pinfunction "2_2") (pintype "passive"))
      (node (ref "C15") (pin "2") (pinfunction "2_2") (pintype "passive"))
      (node (ref "C16") (pin "2") (pinfunction "2_2") (pintype "passive"))
      (node (ref "C17") (pin "2") (pinfunction "2_2") (pintype "passive"))
      (node (ref "C18") (pin "2") (pinfunction "2_2") (pintype "passive"))
      (node (ref "C19") (pin "2") (pinfunction "2_2") (pintype "passive"))
      (node (ref "C2") (pin "1") (pinfunction "1_1") (pintype "passive"))
      (node (ref "C20") (pin "2") (pinfunction "2_2") (pintype "passive"))
      (node (ref "C21") (pin "2") (pinfunction "2_2") (pintype "passive"))
      (node (ref "C22") (pin "2") (pinfunction "2_2") (pintype "passive"))
      (node (ref "C23") (pin "1") (pinfunction "1_1") (pintype "passive"))
      (node (ref "C24") (pin "1") (pinfunction "1_1") (pintype "passive"))
      (node (ref "C3") (pin "2") (pinfunction "2_2") (pintype "passive"))
      (node (ref "C4") (pin "2") (pinfunction "2_2") (pintype "passive"))
      (node (ref "C5") (pin "2") (pinfunction "2_2") (pintype "passive"))
      (node (ref "C6") (pin "2") (pinfunction "2_2") (pintype "passive"))
      (node (ref "C7") (pin "1") (pinfunction "1_1") (pintype "passive"))
      (node (ref "C8") (pin "2") (pinfunction "2_2") (pintype "passive"))
      (node (ref "C9") (pin "1") (pinfunction "1_1") (pintype "passive"))
      (node (ref "D10") (pin "1") (pinfunction "A_1") (pintype "passive"))
      (node (ref "D11") (pin "1") (pinfunction "A_1") (pintype "passive"))
      (node (ref "D12") (pin "1") (pinfunction "A_1") (pintype "passive"))
      (node (ref "D2") (pin "1") (pinfunction "A_1") (pintype "passive"))
      (node (ref "D4") (pin "1") (pinfunction "A_1") (pintype "passive"))
      (node (ref "D6") (pin "1") (pinfunction "A_1") (pintype "passive"))
      (node (ref "D7") (pin "1") (pinfunction "A_1") (pintype "passive"))
      (node (ref "D9") (pin "1") (pinfunction "A_1") (pintype "passive"))
      (node (ref "J1") (pin "14") (pinfunction "14_14") (pintype "passive"))
      (node (ref "J2") (pin "12") (pinfunction "12_12") (pintype "passive"))
      (node (ref "J2") (pin "14") (pinfunction "14_14") (pintype "passive"))
      (node (ref "J3") (pin "3") (pinfunction "3_3") (pintype "passive"))
      (node (ref "J4") (pin "1") (pinfunction "1_1") (pintype "passive"))
      (node (ref "J5") (pin "1") (pinfunction "1_1") (pintype "passive"))
      (node (ref "LED4") (pin "2") (pinfunction "K_2") (pintype "passive"))
      (node (ref "Q1") (pin "2") (pinfunction "S_2") (pintype "passive"))
      (node (ref "Q2") (pin "2") (pinfunction "S_2") (pintype "passive"))
      (node (ref "Q3") (pin "2") (pinfunction "S_2") (pintype "passive"))
      (node (ref "Q4") (pin "2") (pinfunction "S_2") (pintype "passive"))
      (node (ref "Q5") (pin "2") (pinfunction "S_2") (pintype "passive"))
      (node (ref "Q6") (pin "2") (pinfunction "S_2") (pintype "passive"))
      (node (ref "Q7") (pin "2") (pinfunction "S_2") (pintype "passive"))
      (node (ref "R1") (pin "1") (pinfunction "1_1") (pintype "passive"))
      (node (ref "R11") (pin "1") (pinfunction "1_1") (pintype "passive"))
      (node (ref "R13") (pin "1") (pinfunction "1_1") (pintype "passive"))
      (node (ref "R14") (pin "2") (pinfunction "2_2") (pintype "passive"))
      (node (ref "R15") (pin "2") (pinfunction "2_2") (pintype "passive"))
      (node (ref "R18") (pin "2") (pinfunction "2_2") (pintype "passive"))
      (node (ref "R2") (pin "2") (pinfunction "2_2") (pintype "passive"))
      (node (ref "R24") (pin "2") (pinfunction "2_2") (pintype "passive"))
      (node (ref "R28") (pin "2") (pinfunction "2_2") (pintype "passive"))
      (node (ref "R34") (pin "2") (pinfunction "2_2") (pintype "passive"))
      (node (ref "R35") (pin "2") (pinfunction "2_2") (pintype "passive"))
      (node (ref "R45") (pin "2") (pinfunction "2_2") (pintype "passive"))
      (node (ref "R46") (pin "2") (pinfunction "2_2") (pintype "passive"))
      (node (ref "R6") (pin "2") (pinfunction "2_2") (pintype "passive"))
      (node (ref "S1") (pin "1") (pintype "passive"))
      (node (ref "U1") (pin "2") (pinfunction "GND_2") (pintype "power_in"))
      (node (ref "U2") (pin "4") (pinfunction "GND_4") (pintype "power_in"))
      (node (ref "U3") (pin "2") (pinfunction "GND_2") (pintype "power_in"))
      (node (ref "U4") (pin "20") (pinfunction "AVSS_20") (pintype "passive"))
      (node (ref "U4") (pin "25") (pinfunction "VSS_25") (pintype "passive"))
      (node (ref "U4") (pin "41") (pinfunction "VSS_41") (pintype "passive"))
      (node (ref "U4") (pin "56") (pinfunction "VSS_56") (pintype "passive"))
      (node (ref "U4") (pin "9") (pinfunction "VSS_9") (pintype "passive"))
      (node (ref "U5") (pin "2") (pinfunction "Vss_2") (pintype "passive"))
    )
    (net (code "62") (name "Net-(C2-Pad2)") (class "Default")
      (node (ref "C2") (pin "2") (pinfunction "2_2") (pintype "passive"))
      (node (ref "R3") (pin "2") (pinfunction "2_2") (pintype "passive"))
      (node (ref "R8") (pin "2") (pinfunction "2_2") (pintype "passive"))
      (node (ref "R9") (pin "2") (pinfunction "2_2") (pintype "passive"))
    )
    (net (code "63") (name "Net-(C9-Pad2)") (class "Default")
      (node (ref "C9") (pin "2") (pinfunction "2_2") (pintype "passive"))
      (node (ref "R16") (pin "2") (pinfunction "2_2") (pintype "passive"))
      (node (ref "R19") (pin "2") (pinfunction "2_2") (pintype "passive"))
      (node (ref "R20") (pin "2") (pinfunction "2_2") (pintype "passive"))
    )
    (net (code "64") (name "Net-(D2-K)") (class "Default")
      (node (ref "D2") (pin "2") (pinfunction "K_2") (pintype "passive"))
      (node (ref "L1") (pin "1") (pinfunction "1_1") (pintype "passive"))
      (node (ref "U2") (pin "2") (pinfunction "SWE_2") (pintype "open_emitter"))
    )
    (net (code "65") (name "Net-(D3-K)") (class "Default")
      (node (ref "D3") (pin "2") (pinfunction "K_2") (pintype "passive"))
      (node (ref "R21") (pin "2") (pinfunction "2_2") (pintype "passive"))
    )
    (net (code "66") (name "Net-(D5-K)") (class "Default")
      (node (ref "D5") (pin "2") (pinfunction "K_2") (pintype "passive"))
      (node (ref "R25") (pin "2") (pinfunction "2_2") (pintype "passive"))
    )
    (net (code "67") (name "Net-(D8-K)") (class "Default")
      (node (ref "D8") (pin "2") (pinfunction "K_2") (pintype "passive"))
      (node (ref "R29") (pin "2") (pinfunction "2_2") (pintype "passive"))
    )
    (net (code "68") (name "Net-(D14-A)") (class "Default")
      (node (ref "C24") (pin "2") (pinfunction "2_2") (pintype "passive"))
      (node (ref "D14") (pin "1") (pinfunction "A_1") (pintype "passive"))
      (node (ref "R43") (pin "1") (pinfunction "1_1") (pintype "passive"))
      (node (ref "S1") (pin "2") (pintype "passive"))
      (node (ref "U5") (pin "3") (pinfunction "~{MR}_3") (pintype "passive"))
    )
    (net (code "69") (name "Net-(LED1-K)") (class "Default")
      (node (ref "LED1") (pin "2") (pinfunction "K_2") (pintype "passive"))
      (node (ref "R5") (pin "1") (pinfunction "1_1") (pintype "passive"))
    )
    (net (code "70") (name "Net-(LED2-K)") (class "Default")
      (node (ref "LED2") (pin "2") (pinfunction "K_2") (pintype "passive"))
      (node (ref "R15") (pin "1") (pinfunction "1_1") (pintype "passive"))
    )
    (net (code "71") (name "Net-(LED3-K)") (class "Default")
      (node (ref "LED3") (pin "2") (pinfunction "K_2") (pintype "passive"))
      (node (ref "R17") (pin "1") (pinfunction "1_1") (pintype "passive"))
    )
    (net (code "72") (name "Net-(LED4-A)") (class "Default")
      (node (ref "LED4") (pin "1") (pinfunction "A_1") (pintype "passive"))
      (node (ref "R12") (pin "2") (pinfunction "2_2") (pintype "passive"))
    )
    (net (code "73") (name "Net-(LED5-K)") (class "Default")
      (node (ref "LED5") (pin "2") (pinfunction "K_2") (pintype "passive"))
      (node (ref "R30") (pin "1") (pinfunction "1_1") (pintype "passive"))
    )
    (net (code "74") (name "Net-(Q1-G)") (class "Default")
      (node (ref "Q1") (pin "3") (pinfunction "G_3") (pintype "passive"))
      (node (ref "R10") (pin "2") (pinfunction "2_2") (pintype "passive"))
    )
    (net (code "75") (name "Net-(Q4-D)") (class "Default")
      (node (ref "Q4") (pin "1") (pinfunction "D_1") (pintype "passive"))
      (node (ref "R21") (pin "1") (pinfunction "1_1") (pintype "passive"))
      (node (ref "R25") (pin "1") (pinfunction "1_1") (pintype "passive"))
      (node (ref "R29") (pin "1") (pinfunction "1_1") (pintype "passive"))
    )
    (net (code "76") (name "Net-(U1-RS)") (class "Default")
      (node (ref "R6") (pin "1") (pinfunction "1_1") (pintype "passive"))
      (node (ref "U1") (pin "8") (pinfunction "RS_8") (pintype "passive"))
    )
    (net (code "77") (name "Net-(U1-VREF)") (class "Default")
      (node (ref "R3") (pin "1") (pinfunction "1_1") (pintype "passive"))
      (node (ref "U1") (pin "5") (pinfunction "VREF_5") (pintype "output"))
    )
    (net (code "78") (name "Net-(U2--VIN)") (class "Default")
      (node (ref "R11") (pin "2") (pinfunction "2_2") (pintype "passive"))
      (node (ref "R7") (pin "2") (pinfunction "2_2") (pintype "passive"))
      (node (ref "U2") (pin "5") (pinfunction "-VIN_5") (pintype "input"))
    )
    (net (code "79") (name "Net-(U2-DRVC)") (class "Default")
      (node (ref "R4") (pin "1") (pinfunction "1_1") (pintype "passive"))
      (node (ref "U2") (pin "1") (pinfunction "SWC_1") (pintype "open_collector"))
      (node (ref "U2") (pin "7") (pinfunction "IPK_7") (pintype "passive"))
      (node (ref "U2") (pin "8") (pinfunction "DRVC_8") (pintype "open_collector"))
    )
    (net (code "80") (name "Net-(U2-TCAP)") (class "Default")
      (node (ref "C7") (pin "2") (pinfunction "2_2") (pintype "passive"))
      (node (ref "U2") (pin "3") (pinfunction "TCAP_3") (pintype "passive"))
    )
    (net (code "81") (name "Net-(U3-RS)") (class "Default")
      (node (ref "R18") (pin "1") (pinfunction "1_1") (pintype "passive"))
      (node (ref "U3") (pin "8") (pinfunction "RS_8") (pintype "passive"))
    )
    (net (code "82") (name "Net-(U3-VREF)") (class "Default")
      (node (ref "R16") (pin "1") (pinfunction "1_1") (pintype "passive"))
      (node (ref "U3") (pin "5") (pinfunction "VREF_5") (pintype "output"))
    )
    (net (code "83") (name "Net-(U4-OSC1{slash}CLKI)") (class "Default")
      (node (ref "C17") (pin "1") (pinfunction "1_1") (pintype "passive"))
      (node (ref "U4") (pin "39") (pinfunction "OSC1/CLKI_39") (pintype "passive"))
      (node (ref "Y1") (pin "2") (pinfunction "OSC2_2") (pintype "passive"))
    )
    (net (code "84") (name "Net-(U4-OSC2{slash}CLKO{slash}RC15)") (class "Default")
      (node (ref "C18") (pin "1") (pinfunction "1_1") (pintype "passive"))
      (node (ref "U4") (pin "40") (pinfunction "OSC2/CLKO/RC15_40") (pintype "passive"))
      (node (ref "Y1") (pin "1") (pinfunction "OSC1_1") (pintype "passive"))
    )
    (net (code "85") (name "Net-(U4-SCL{slash}RG2)") (class "Default")
      (node (ref "R30") (pin "2") (pinfunction "2_2") (pintype "passive"))
      (node (ref "U4") (pin "37") (pinfunction "SCL/RG2_37") (pintype "passive"))
    )
    (net (code "86") (name "Net-(U4-~{SS2}{slash}CN11{slash}RG9)") (class "Default")
      (node (ref "R33") (pin "2") (pinfunction "2_2") (pintype "passive"))
      (node (ref "U4") (pin "8") (pinfunction "~{SS2}/CN11/RG9_8") (pintype "passive"))
    )
    (net (code "87") (name "unconnected-(U3-RXD-Pad4)") (class "Default")
      (node (ref "U3") (pin "4") (pinfunction "RXD_4") (pintype "output+no_connect"))
    )
    (net (code "88") (name "unconnected-(U3-TXD-Pad1)") (class "Default")
      (node (ref "U3") (pin "1") (pinfunction "TXD_1") (pintype "input+no_connect"))
    )
    (net (code "89") (name "unconnected-(U4-AN0{slash}VREF+{slash}CN2{slash}RB0-Pad16)") (class "Default")
      (node (ref "U4") (pin "16") (pinfunction "AN0/VREF+/CN2/RB0_16") (pintype "passive+no_connect"))
    )
    (net (code "90") (name "unconnected-(U4-AN1{slash}VREF-{slash}CN3{slash}RB1-Pad15)") (class "Default")
      (node (ref "U4") (pin "15") (pinfunction "AN1/VREF-/CN3/RB1_15") (pintype "passive+no_connect"))
    )
    (net (code "91") (name "unconnected-(U4-AN2{slash}~{SS1}{slash}LVDIN{slash}CN4{slash}RB2-Pad14)") (class "Default")
      (node (ref "U4") (pin "14") (pinfunction "AN2/~{SS1}/LVDIN/CN4/RB2_14") (pintype "passive+no_connect"))
    )
    (net (code "92") (name "unconnected-(U4-AN3{slash}CN5{slash}RB3-Pad13)") (class "Default")
      (node (ref "U4") (pin "13") (pinfunction "AN3/CN5/RB3_13") (pintype "passive+no_connect"))
    )
    (net (code "93") (name "unconnected-(U4-AN4{slash}IC7{slash}CN6{slash}RB4-Pad12)") (class "Default")
      (node (ref "U4") (pin "12") (pinfunction "AN4/IC7/CN6/RB4_12") (pintype "passive+no_connect"))
    )
    (net (code "94") (name "unconnected-(U4-AN5{slash}IC8{slash}CN7{slash}RB5-Pad11)") (class "Default")
      (node (ref "U4") (pin "11") (pinfunction "AN5/IC8/CN7/RB5_11") (pintype "passive+no_connect"))
    )
    (net (code "95") (name "unconnected-(U4-AN8{slash}RB8-Pad21)") (class "Default")
      (node (ref "U4") (pin "21") (pinfunction "AN8/RB8_21") (pintype "passive+no_connect"))
    )
    (net (code "96") (name "unconnected-(U4-AN9{slash}RB9-Pad22)") (class "Default")
      (node (ref "U4") (pin "22") (pinfunction "AN9/RB9_22") (pintype "passive+no_connect"))
    )
    (net (code "97") (name "unconnected-(U4-AN10{slash}RB10-Pad23)") (class "Default")
      (node (ref "U4") (pin "23") (pinfunction "AN10/RB10_23") (pintype "passive+no_connect"))
    )
    (net (code "98") (name "unconnected-(U4-AN11{slash}RB11-Pad24)") (class "Default")
      (node (ref "U4") (pin "24") (pinfunction "AN11/RB11_24") (pintype "passive+no_connect"))
    )
    (net (code "99") (name "unconnected-(U4-AN12{slash}RB12-Pad27)") (class "Default")
      (node (ref "U4") (pin "27") (pinfunction "AN12/RB12_27") (pintype "passive+no_connect"))
    )
    (net (code "100") (name "unconnected-(U4-AN13{slash}RB13-Pad28)") (class "Default")
      (node (ref "U4") (pin "28") (pinfunction "AN13/RB13_28") (pintype "passive+no_connect"))
    )
    (net (code "101") (name "unconnected-(U4-AN14{slash}RB14-Pad29)") (class "Default")
      (node (ref "U4") (pin "29") (pinfunction "AN14/RB14_29") (pintype "passive+no_connect"))
    )
    (net (code "102") (name "unconnected-(U4-AN15{slash}OCFB{slash}CN12{slash}RB15-Pad30)") (class "Default")
      (node (ref "U4") (pin "30") (pinfunction "AN15/OCFB/CN12/RB15_30") (pintype "passive+no_connect"))
    )
    (net (code "103") (name "unconnected-(U4-C1RX{slash}RF0-Pad58)") (class "Default")
      (node (ref "U4") (pin "58") (pinfunction "C1RX/RF0_58") (pintype "passive+no_connect"))
    )
    (net (code "104") (name "unconnected-(U4-C1TX{slash}RF1-Pad59)") (class "Default")
      (node (ref "U4") (pin "59") (pinfunction "C1TX/RF1_59") (pintype "passive+no_connect"))
    )
    (net (code "105") (name "unconnected-(U4-C2RX{slash}RG0-Pad61)") (class "Default")
      (node (ref "U4") (pin "61") (pinfunction "C2RX/RG0_61") (pintype "passive+no_connect"))
    )
    (net (code "106") (name "unconnected-(U4-C2TX{slash}RG1-Pad60)") (class "Default")
      (node (ref "U4") (pin "60") (pinfunction "C2TX/RG1_60") (pintype "passive+no_connect"))
    )
    (net (code "107") (name "unconnected-(U4-COFS{slash}RG15-Pad1)") (class "Default")
      (node (ref "U4") (pin "1") (pinfunction "COFS/RG15_1") (pintype "passive"))
    )
    (net (code "108") (name "unconnected-(U4-CSCK{slash}RG14-Pad62)") (class "Default")
      (node (ref "U4") (pin "62") (pinfunction "CSCK/RG14_62") (pintype "passive"))
    )
    (net (code "109") (name "unconnected-(U4-CSDI{slash}RG12-Pad63)") (class "Default")
      (node (ref "U4") (pin "63") (pinfunction "CSDI/RG12_63") (pintype "passive"))
    )
    (net (code "110") (name "unconnected-(U4-CSDO{slash}RG13-Pad64)") (class "Default")
      (node (ref "U4") (pin "64") (pinfunction "CSDO/RG13_64") (pintype "passive"))
    )
    (net (code "111") (name "unconnected-(U4-EMUC1{slash}SOSCO{slash}T1CK{slash}CN0{slash}RC14-Pad48)") (class "Default")
      (node (ref "U4") (pin "48") (pinfunction "EMUC1/SOSCO/T1CK/CN0/RC14_48") (pintype "passive+no_connect"))
    )
    (net (code "112") (name "unconnected-(U4-EMUC2{slash}OC1{slash}RD0-Pad46)") (class "Default")
      (node (ref "U4") (pin "46") (pinfunction "EMUC2/OC1/RD0_46") (pintype "passive+no_connect"))
    )
    (net (code "113") (name "unconnected-(U4-EMUC3{slash}SCK1{slash}INT0{slash}RF6-Pad35)") (class "Default")
      (node (ref "U4") (pin "35") (pinfunction "EMUC3/SCK1/INT0/RF6_35") (pintype "passive"))
    )
    (net (code "114") (name "unconnected-(U4-EMUD1{slash}SOSCI{slash}T4CK{slash}CN1{slash}RC13-Pad47)") (class "Default")
      (node (ref "U4") (pin "47") (pinfunction "EMUD1/SOSCI/T4CK/CN1/RC13_47") (pintype "passive+no_connect"))
    )
    (net (code "115") (name "unconnected-(U4-EMUD2{slash}OC2{slash}RD1-Pad49)") (class "Default")
      (node (ref "U4") (pin "49") (pinfunction "EMUD2/OC2/RD1_49") (pintype "passive+no_connect"))
    )
    (net (code "116") (name "unconnected-(U4-EMUD3{slash}U1TX{slash}SDO1{slash}RF3-Pad33)") (class "Default")
      (node (ref "U4") (pin "33") (pinfunction "EMUD3/U1TX/SDO1/RF3_33") (pintype "passive+no_connect"))
    )
    (net (code "117") (name "unconnected-(U4-IC1{slash}INT1{slash}RD8-Pad42)") (class "Default")
      (node (ref "U4") (pin "42") (pinfunction "IC1/INT1/RD8_42") (pintype "passive+no_connect"))
    )
    (net (code "118") (name "unconnected-(U4-IC2{slash}INT2{slash}RD9-Pad43)") (class "Default")
      (node (ref "U4") (pin "43") (pinfunction "IC2/INT2/RD9_43") (pintype "passive+no_connect"))
    )
    (net (code "119") (name "unconnected-(U4-IC3{slash}INT3{slash}RD10-Pad44)") (class "Default")
      (node (ref "U4") (pin "44") (pinfunction "IC3/INT3/RD10_44") (pintype "passive+no_connect"))
    )
    (net (code "120") (name "unconnected-(U4-IC4{slash}INT4{slash}RD11-Pad45)") (class "Default")
      (node (ref "U4") (pin "45") (pinfunction "IC4/INT4/RD11_45") (pintype "passive+no_connect"))
    )
    (net (code "121") (name "unconnected-(U4-OC3{slash}RD2-Pad50)") (class "Default")
      (node (ref "U4") (pin "50") (pinfunction "OC3/RD2_50") (pintype "passive+no_connect"))
    )
    (net (code "122") (name "unconnected-(U4-OC4{slash}RD3-Pad51)") (class "Default")
      (node (ref "U4") (pin "51") (pinfunction "OC4/RD3_51") (pintype "passive+no_connect"))
    )
    (net (code "123") (name "unconnected-(U4-OC5{slash}IC5{slash}CN13{slash}RD4-Pad52)") (class "Default")
      (node (ref "U4") (pin "52") (pinfunction "OC5/IC5/CN13/RD4_52") (pintype "passive+no_connect"))
    )
    (net (code "124") (name "unconnected-(U4-OC6{slash}IC6{slash}CN14{slash}RD5-Pad53)") (class "Default")
      (node (ref "U4") (pin "53") (pinfunction "OC6/IC6/CN14/RD5_53") (pintype "passive+no_connect"))
    )
    (net (code "125") (name "unconnected-(U4-OC7{slash}CN15{slash}RD6-Pad54)") (class "Default")
      (node (ref "U4") (pin "54") (pinfunction "OC7/CN15/RD6_54") (pintype "passive+no_connect"))
    )
    (net (code "126") (name "unconnected-(U4-OC8{slash}CN16{slash}RD7-Pad55)") (class "Default")
      (node (ref "U4") (pin "55") (pinfunction "OC8/CN16/RD7_55") (pintype "passive+no_connect"))
    )
    (net (code "127") (name "unconnected-(U4-PGC{slash}EMUC{slash}AN6{slash}OCFA{slash}RB6-Pad17)") (class "Default")
      (node (ref "U4") (pin "17") (pinfunction "PGC/EMUC/AN6/OCFA/RB6_17") (pintype "passive+no_connect"))
    )
    (net (code "128") (name "unconnected-(U4-PGD{slash}EMUD{slash}AN7{slash}RB7-Pad18)") (class "Default")
      (node (ref "U4") (pin "18") (pinfunction "PGD/EMUD/AN7/RB7_18") (pintype "passive+no_connect"))
    )
    (net (code "129") (name "unconnected-(U4-SCK2{slash}CN8{slash}RG6-Pad4)") (class "Default")
      (node (ref "U4") (pin "4") (pinfunction "SCK2/CN8/RG6_4") (pintype "passive"))
    )
    (net (code "130") (name "unconnected-(U4-SDA{slash}RG3-Pad36)") (class "Default")
      (node (ref "U4") (pin "36") (pinfunction "SDA/RG3_36") (pintype "passive"))
    )
    (net (code "131") (name "unconnected-(U4-SDI2{slash}CN9{slash}RG7-Pad5)") (class "Default")
      (node (ref "U4") (pin "5") (pinfunction "SDI2/CN9/RG7_5") (pintype "passive"))
    )
    (net (code "132") (name "unconnected-(U4-SDO2{slash}CN10{slash}RG8-Pad6)") (class "Default")
      (node (ref "U4") (pin "6") (pinfunction "SDO2/CN10/RG8_6") (pintype "passive"))
    )
    (net (code "133") (name "unconnected-(U4-T2CK{slash}RC1-Pad2)") (class "Default")
      (node (ref "U4") (pin "2") (pinfunction "T2CK/RC1_2") (pintype "passive"))
    )
    (net (code "134") (name "unconnected-(U4-T3CK{slash}RC2-Pad3)") (class "Default")
      (node (ref "U4") (pin "3") (pinfunction "T3CK/RC2_3") (pintype "passive"))
    )
    (net (code "135") (name "unconnected-(U4-U1RX{slash}SDI1{slash}RF2-Pad34)") (class "Default")
      (node (ref "U4") (pin "34") (pinfunction "U1RX/SDI1/RF2_34") (pintype "passive+no_connect"))
    )
    (net (code "136") (name "unconnected-(U4-U2RX{slash}CN17{slash}RF4-Pad31)") (class "Default")
      (node (ref "U4") (pin "31") (pinfunction "U2RX/CN17/RF4_31") (pintype "passive+no_connect"))
    )
    (net (code "137") (name "unconnected-(U4-U2TX{slash}CN18{slash}RF5-Pad32)") (class "Default")
      (node (ref "U4") (pin "32") (pinfunction "U2TX/CN18/RF5_32") (pintype "passive+no_connect"))
    )
    (net (code "138") (name "unconnected-(U4-~{MCLR}-Pad7)") (class "Default")
      (node (ref "U4") (pin "7") (pinfunction "~{MCLR}_7") (pintype "passive+no_connect"))
    )
    (net (code "139") (name "unconnected-(U5-WDI-Pad4)") (class "Default")
      (node (ref "U5") (pin "4") (pinfunction "WDI_4") (pintype "passive+no_connect"))
    )
    (net (code "140") (name "unconnected-(U5-~{RST}-Pad1)") (class "Default")
      (node (ref "U5") (pin "1") (pinfunction "~{RST}_1") (pintype "passive+no_connect"))
    )
  )
)
